# ProtoScrewShield.net
KiCad netlist of a schematic drawn in EAGLE
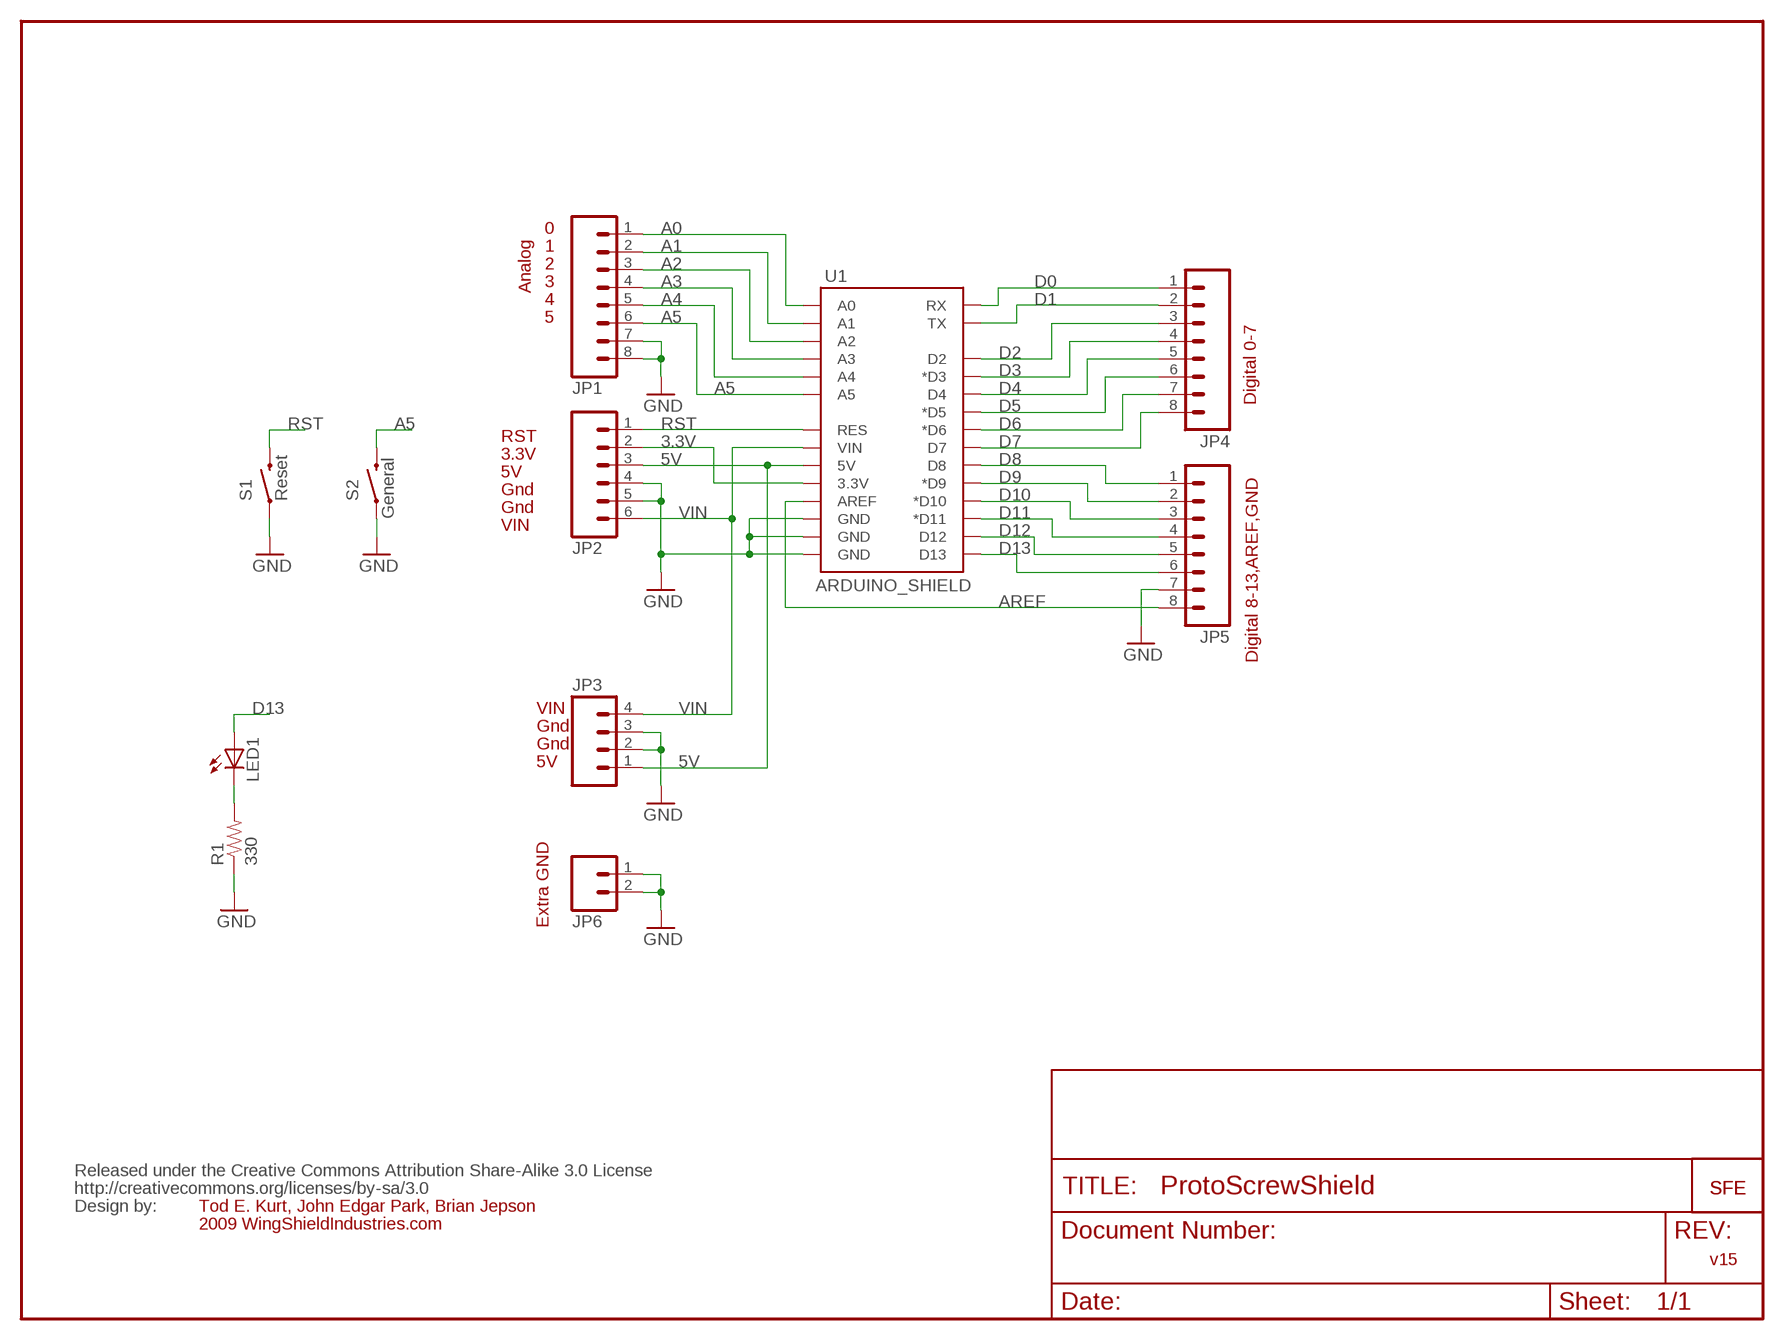
[diagram p0: schematic, sheet 1]

(export (version "E")
  (design (tool "Eeschema 10.0.6"))
  (components
    (comp (ref "JP1")
      (value "M083.5MM-8")
      (footprint "eagle-import:SCREWTERMINAL-3.5MM-8")
      (libsource (lib "eagle-import") (part "M083.5MM-8"))
    )
    (comp (ref "JP2")
      (value "M063.5MM-6")
      (footprint "eagle-import:SCREWTERMINAL-3.5MM-6")
      (libsource (lib "eagle-import") (part "M063.5MM-6"))
    )
    (comp (ref "JP3")
      (value "M04SCREW")
      (footprint "eagle-import:SCREWTERMINAL-3.5MM-4")
      (libsource (lib "eagle-import") (part "M04SCREW"))
    )
    (comp (ref "JP4")
      (value "M083.5MM-8")
      (footprint "eagle-import:SCREWTERMINAL-3.5MM-8")
      (libsource (lib "eagle-import") (part "M083.5MM-8"))
    )
    (comp (ref "JP5")
      (value "M083.5MM-8")
      (footprint "eagle-import:SCREWTERMINAL-3.5MM-8")
      (libsource (lib "eagle-import") (part "M083.5MM-8"))
    )
    (comp (ref "JP6")
      (value "M023.5MM")
      (footprint "eagle-import:SCREWTERMINAL-3.5MM-2")
      (libsource (lib "eagle-import") (part "M023.5MM"))
    )
    (comp (ref "JP7")
      (value "LOGO-SFENEW")
      (footprint "eagle-import:SFE-NEW-WEBLOGO")
      (libsource (lib "eagle-import") (part "LOGO-SFENEW"))
    )
    (comp (ref "JP8")
      (value "LOGO-SFESK")
      (footprint "eagle-import:SFE-LOGO-FLAME")
      (libsource (lib "eagle-import") (part "LOGO-SFESK"))
    )
    (comp (ref "LED1")
      (value "LED5MM")
      (footprint "eagle-import:LED5MM")
      (libsource (lib "eagle-import") (part "LED5MM"))
    )
    (comp (ref "R1")
      (value "330")
      (footprint "eagle-import:AXIAL-0.3")
      (libsource (lib "eagle-import") (part "RESISTORPTH1"))
    )
    (comp (ref "S1")
      (value "Reset")
      (footprint "eagle-import:TACTILE-PTH")
      (libsource (lib "eagle-import") (part "SWITCH-MOMENTARY-2PTH"))
    )
    (comp (ref "S2")
      (value "General")
      (footprint "eagle-import:TACTILE-PTH")
      (libsource (lib "eagle-import") (part "SWITCH-MOMENTARY-2PTH"))
    )
    (comp (ref "U$1")
      (value "CREATIVE_COMMONS")
      (footprint "eagle-import:CREATIVE_COMMONS")
      (libsource (lib "eagle-import") (part "CREATIVE_COMMONS"))
    )
    (comp (ref "U1")
      (value "ARDUINO_SHIELD")
      (footprint "eagle-import:DUEMILANOVE_SHIELD_NOHOLES")
      (libsource (lib "eagle-import") (part "ARDUINO_SHIELDNOHOLES"))
    )
  )
  (nets
    (net (code "1") (name "/3.3V") (class "Default")
      (node (ref "JP2") (pin "2") (pinfunction "2_2") (pintype "passive"))
      (node (ref "U1") (pin "3.3V") (pinfunction "3.3V_3.3V") (pintype "bidirectional"))
    )
    (net (code "2") (name "/5V") (class "Default")
      (node (ref "JP2") (pin "3") (pinfunction "3_3") (pintype "passive"))
      (node (ref "JP3") (pin "1") (pinfunction "1_1") (pintype "passive"))
      (node (ref "U1") (pin "5V") (pinfunction "5V_5V") (pintype "bidirectional"))
    )
    (net (code "3") (name "/A0") (class "Default")
      (node (ref "JP1") (pin "1") (pinfunction "1_1") (pintype "passive"))
      (node (ref "U1") (pin "A0") (pinfunction "A0_A0") (pintype "bidirectional"))
    )
    (net (code "4") (name "/A1") (class "Default")
      (node (ref "JP1") (pin "2") (pinfunction "2_2") (pintype "passive"))
      (node (ref "U1") (pin "A1") (pinfunction "A1_A1") (pintype "bidirectional"))
    )
    (net (code "5") (name "/A2") (class "Default")
      (node (ref "JP1") (pin "3") (pinfunction "3_3") (pintype "passive"))
      (node (ref "U1") (pin "A2") (pinfunction "A2_A2") (pintype "bidirectional"))
    )
    (net (code "6") (name "/A3") (class "Default")
      (node (ref "JP1") (pin "4") (pinfunction "4_4") (pintype "passive"))
      (node (ref "U1") (pin "A3") (pinfunction "A3_A3") (pintype "bidirectional"))
    )
    (net (code "7") (name "/A4") (class "Default")
      (node (ref "JP1") (pin "5") (pinfunction "5_5") (pintype "passive"))
      (node (ref "U1") (pin "A4") (pinfunction "A4_A4") (pintype "bidirectional"))
    )
    (net (code "8") (name "/A5") (class "Default")
      (node (ref "JP1") (pin "6") (pinfunction "6_6") (pintype "passive"))
      (node (ref "S2") (pin "3") (pinfunction "2_3") (pintype "passive"))
      (node (ref "U1") (pin "A5") (pinfunction "A5_A5") (pintype "bidirectional"))
    )
    (net (code "9") (name "/AREF") (class "Default")
      (node (ref "JP5") (pin "8") (pinfunction "8_8") (pintype "passive"))
      (node (ref "U1") (pin "AREF") (pinfunction "AREF_AREF") (pintype "bidirectional"))
    )
    (net (code "10") (name "/D0") (class "Default")
      (node (ref "JP4") (pin "1") (pinfunction "1_1") (pintype "passive"))
      (node (ref "U1") (pin "RX") (pinfunction "RX_RX") (pintype "bidirectional"))
    )
    (net (code "11") (name "/D1") (class "Default")
      (node (ref "JP4") (pin "2") (pinfunction "2_2") (pintype "passive"))
      (node (ref "U1") (pin "TX") (pinfunction "TX_TX") (pintype "bidirectional"))
    )
    (net (code "12") (name "/D2") (class "Default")
      (node (ref "JP4") (pin "3") (pinfunction "3_3") (pintype "passive"))
      (node (ref "U1") (pin "D2") (pinfunction "D2_D2") (pintype "bidirectional"))
    )
    (net (code "13") (name "/D3") (class "Default")
      (node (ref "JP4") (pin "4") (pinfunction "4_4") (pintype "passive"))
      (node (ref "U1") (pin "D3") (pinfunction "*D3_D3") (pintype "bidirectional"))
    )
    (net (code "14") (name "/D4") (class "Default")
      (node (ref "JP4") (pin "5") (pinfunction "5_5") (pintype "passive"))
      (node (ref "U1") (pin "D4") (pinfunction "D4_D4") (pintype "bidirectional"))
    )
    (net (code "15") (name "/D5") (class "Default")
      (node (ref "JP4") (pin "6") (pinfunction "6_6") (pintype "passive"))
      (node (ref "U1") (pin "D5") (pinfunction "*D5_D5") (pintype "bidirectional"))
    )
    (net (code "16") (name "/D6") (class "Default")
      (node (ref "JP4") (pin "7") (pinfunction "7_7") (pintype "passive"))
      (node (ref "U1") (pin "D6") (pinfunction "*D6_D6") (pintype "bidirectional"))
    )
    (net (code "17") (name "/D7") (class "Default")
      (node (ref "JP4") (pin "8") (pinfunction "8_8") (pintype "passive"))
      (node (ref "U1") (pin "D7") (pinfunction "D7_D7") (pintype "bidirectional"))
    )
    (net (code "18") (name "/D8") (class "Default")
      (node (ref "JP5") (pin "1") (pinfunction "1_1") (pintype "passive"))
      (node (ref "U1") (pin "D8") (pinfunction "D8_D8") (pintype "bidirectional"))
    )
    (net (code "19") (name "/D9") (class "Default")
      (node (ref "JP5") (pin "2") (pinfunction "2_2") (pintype "passive"))
      (node (ref "U1") (pin "D9") (pinfunction "*D9_D9") (pintype "bidirectional"))
    )
    (net (code "20") (name "/D10") (class "Default")
      (node (ref "JP5") (pin "3") (pinfunction "3_3") (pintype "passive"))
      (node (ref "U1") (pin "D10") (pinfunction "*D10_D10") (pintype "bidirectional"))
    )
    (net (code "21") (name "/D11") (class "Default")
      (node (ref "JP5") (pin "4") (pinfunction "4_4") (pintype "passive"))
      (node (ref "U1") (pin "D11") (pinfunction "*D11_D11") (pintype "bidirectional"))
    )
    (net (code "22") (name "/D12") (class "Default")
      (node (ref "JP5") (pin "5") (pinfunction "5_5") (pintype "passive"))
      (node (ref "U1") (pin "D12") (pinfunction "D12_D12") (pintype "bidirectional"))
    )
    (net (code "23") (name "/D13") (class "Default")
      (node (ref "JP5") (pin "6") (pinfunction "6_6") (pintype "passive"))
      (node (ref "LED1") (pin "A") (pinfunction "A_A") (pintype "passive"))
      (node (ref "U1") (pin "D13") (pinfunction "D13_D13") (pintype "bidirectional"))
    )
    (net (code "24") (name "/RST") (class "Default")
      (node (ref "JP2") (pin "1") (pinfunction "1_1") (pintype "passive"))
      (node (ref "S1") (pin "3") (pinfunction "2_3") (pintype "passive"))
      (node (ref "U1") (pin "RES") (pinfunction "RES_RES") (pintype "bidirectional"))
    )
    (net (code "25") (name "/VIN") (class "Default")
      (node (ref "JP2") (pin "6") (pinfunction "6_6") (pintype "passive"))
      (node (ref "JP3") (pin "4") (pinfunction "4_4") (pintype "passive"))
      (node (ref "U1") (pin "VIN") (pinfunction "VIN_VIN") (pintype "bidirectional"))
    )
    (net (code "26") (name "GND") (class "Default")
      (node (ref "JP1") (pin "7") (pinfunction "7_7") (pintype "passive"))
      (node (ref "JP1") (pin "8") (pinfunction "8_8") (pintype "passive"))
      (node (ref "JP2") (pin "4") (pinfunction "4_4") (pintype "passive"))
      (node (ref "JP2") (pin "5") (pinfunction "5_5") (pintype "passive"))
      (node (ref "JP3") (pin "2") (pinfunction "2_2") (pintype "passive"))
      (node (ref "JP3") (pin "3") (pinfunction "3_3") (pintype "passive"))
      (node (ref "JP5") (pin "7") (pinfunction "7_7") (pintype "passive"))
      (node (ref "JP6") (pin "1") (pinfunction "1_1") (pintype "passive"))
      (node (ref "JP6") (pin "2") (pinfunction "2_2") (pintype "passive"))
      (node (ref "R1") (pin "P$1") (pinfunction "1_P$1") (pintype "passive"))
      (node (ref "S1") (pin "1") (pinfunction "1_1") (pintype "passive"))
      (node (ref "S2") (pin "1") (pinfunction "1_1") (pintype "passive"))
      (node (ref "U1") (pin "GND@0") (pinfunction "GND_GND@0") (pintype "bidirectional"))
      (node (ref "U1") (pin "GND@1") (pinfunction "GND_GND@1") (pintype "bidirectional"))
      (node (ref "U1") (pin "GND@2") (pinfunction "GND_GND@2") (pintype "bidirectional"))
    )
    (net (code "27") (name "Net-(LED1-C)") (class "Default")
      (node (ref "LED1") (pin "K") (pinfunction "C_K") (pintype "passive"))
      (node (ref "R1") (pin "P$2") (pinfunction "2_P$2") (pintype "passive"))
    )
  )
)
